# V001.net
KiCad netlist of a schematic drawn in EAGLE
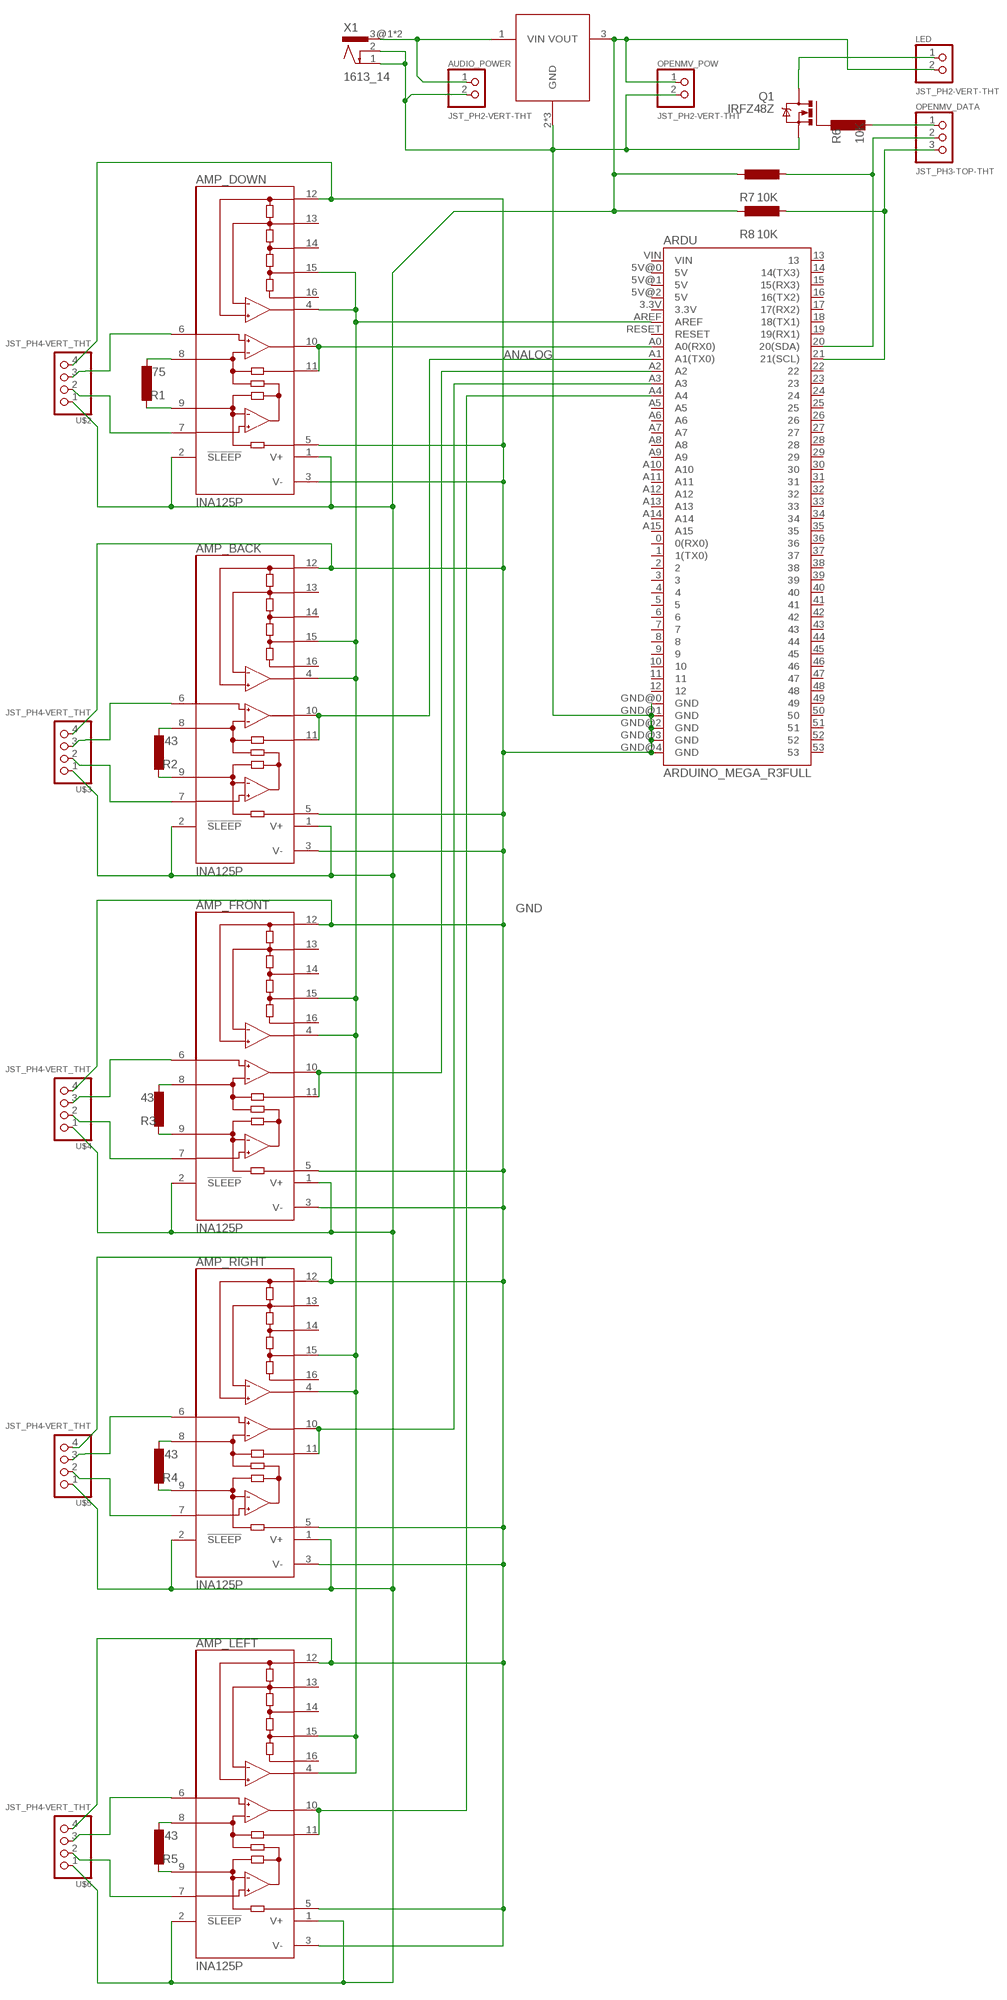
[diagram p0: schematic, sheet 1]

(export (version "E")
  (design (tool "Eeschema 10.0.6"))
  (components
    (comp (ref "AMP_BACK")
      (value "INA125P")
      (footprint "eagle-import:DIL16")
      (fields (field (name "MF") "TEXAS INSTRUMENT CONNECTORS"))
      (libsource (lib "eagle-import") (part "INA125P"))
    )
    (comp (ref "AMP_DOWN")
      (value "INA125P")
      (footprint "eagle-import:DIL16")
      (fields (field (name "MF") "TEXAS INSTRUMENT CONNECTORS"))
      (libsource (lib "eagle-import") (part "INA125P"))
    )
    (comp (ref "AMP_FRONT")
      (value "INA125P")
      (footprint "eagle-import:DIL16")
      (fields (field (name "MF") "TEXAS INSTRUMENT CONNECTORS"))
      (libsource (lib "eagle-import") (part "INA125P"))
    )
    (comp (ref "AMP_LEFT")
      (value "INA125P")
      (footprint "eagle-import:DIL16")
      (fields (field (name "MF") "TEXAS INSTRUMENT CONNECTORS"))
      (libsource (lib "eagle-import") (part "INA125P"))
    )
    (comp (ref "AMP_RIGHT")
      (value "INA125P")
      (footprint "eagle-import:DIL16")
      (fields (field (name "MF") "TEXAS INSTRUMENT CONNECTORS"))
      (libsource (lib "eagle-import") (part "INA125P"))
    )
    (comp (ref "ARDU")
      (value "ARDUINO_MEGA_R3FULL")
      (footprint "eagle-import:ARDUINO_MEGA")
      (libsource (lib "eagle-import") (part "ARDUINO_MEGA_R3FULL"))
    )
    (comp (ref "AUDIO_POWER")
      (value "JST_PH2-VERT-THT")
      (footprint "eagle-import:B2B-PH-K-S")
      (libsource (lib "eagle-import") (part "JST_PH2-VERT-THT"))
    )
    (comp (ref "LED")
      (value "JST_PH2-VERT-THT")
      (footprint "eagle-import:B2B-PH-K-S")
      (libsource (lib "eagle-import") (part "JST_PH2-VERT-THT"))
    )
    (comp (ref "OPENMV_DATA")
      (value "JST_PH3-TOP-THT")
      (footprint "eagle-import:B3B-PH-K-S")
      (libsource (lib "eagle-import") (part "JST_PH3-TOP-THT"))
    )
    (comp (ref "OPENMV_POW")
      (value "JST_PH2-VERT-THT")
      (footprint "eagle-import:B2B-PH-K-S")
      (libsource (lib "eagle-import") (part "JST_PH2-VERT-THT"))
    )
    (comp (ref "Q1")
      (value "IRFZ48Z")
      (footprint "eagle-import:TO220BH")
      (libsource (lib "eagle-import") (part "IRFZ48Z"))
    )
    (comp (ref "R1")
      (value "75")
      (footprint "eagle-import:0207_10")
      (libsource (lib "eagle-import") (part "L-EU0207/10"))
    )
    (comp (ref "R2")
      (value "43")
      (footprint "eagle-import:0207_10")
      (libsource (lib "eagle-import") (part "L-EU0207/10"))
    )
    (comp (ref "R3")
      (value "43")
      (footprint "eagle-import:0207_10")
      (libsource (lib "eagle-import") (part "L-EU0207/10"))
    )
    (comp (ref "R4")
      (value "43")
      (footprint "eagle-import:0207_10")
      (libsource (lib "eagle-import") (part "L-EU0207/10"))
    )
    (comp (ref "R5")
      (value "43")
      (footprint "eagle-import:0207_10")
      (libsource (lib "eagle-import") (part "L-EU0207/10"))
    )
    (comp (ref "R6")
      (value "10K")
      (footprint "eagle-import:0207_10")
      (libsource (lib "eagle-import") (part "L-EU0207/10"))
    )
    (comp (ref "R7")
      (value "10K")
      (footprint "eagle-import:0207_10")
      (libsource (lib "eagle-import") (part "L-EU0207/10"))
    )
    (comp (ref "R8")
      (value "10K")
      (footprint "eagle-import:0207_10")
      (libsource (lib "eagle-import") (part "L-EU0207/10"))
    )
    (comp (ref "U$1")
      (value "TL780")
      (footprint "eagle-import:TO254P1651X1067X470-3")
      (libsource (lib "eagle-import") (part "TL780"))
    )
    (comp (ref "U$2")
      (value "JST_PH4-VERT_THT")
      (footprint "eagle-import:B4B-PH-K-S")
      (libsource (lib "eagle-import") (part "JST_PH4-VERT_THT"))
    )
    (comp (ref "U$3")
      (value "JST_PH4-VERT_THT")
      (footprint "eagle-import:B4B-PH-K-S")
      (libsource (lib "eagle-import") (part "JST_PH4-VERT_THT"))
    )
    (comp (ref "U$4")
      (value "JST_PH4-VERT_THT")
      (footprint "eagle-import:B4B-PH-K-S")
      (libsource (lib "eagle-import") (part "JST_PH4-VERT_THT"))
    )
    (comp (ref "U$5")
      (value "JST_PH4-VERT_THT")
      (footprint "eagle-import:B4B-PH-K-S")
      (libsource (lib "eagle-import") (part "JST_PH4-VERT_THT"))
    )
    (comp (ref "U$6")
      (value "JST_PH4-VERT_THT")
      (footprint "eagle-import:B4B-PH-K-S")
      (libsource (lib "eagle-import") (part "JST_PH4-VERT_THT"))
    )
    (comp (ref "X1")
      (value "1613_14")
      (footprint "eagle-import:1613_14")
      (fields (field (name "MF") "LUMBERG") (field (name "MPN") "1613 14"))
      (libsource (lib "eagle-import") (part "1613_14"))
    )
  )
  (nets
    (net (code "1") (name "/ANALOG") (class "Default")
      (node (ref "AMP_DOWN") (pin "10") (pinfunction "OUT_10") (pintype "output"))
      (node (ref "AMP_DOWN") (pin "11") (pinfunction "SENSE_11") (pintype "passive"))
      (node (ref "ARDU") (pin "A0") (pinfunction "A0(RX0)_A0") (pintype "bidirectional"))
    )
    (net (code "2") (name "/GND") (class "Default")
      (node (ref "AMP_BACK") (pin "12") (pinfunction "REFCOM_12") (pintype "passive"))
      (node (ref "AMP_BACK") (pin "3") (pinfunction "V-_3") (pintype "power_in"))
      (node (ref "AMP_BACK") (pin "5") (pinfunction "REF_5") (pintype "passive"))
      (node (ref "AMP_DOWN") (pin "12") (pinfunction "REFCOM_12") (pintype "passive"))
      (node (ref "AMP_DOWN") (pin "3") (pinfunction "V-_3") (pintype "power_in"))
      (node (ref "AMP_DOWN") (pin "5") (pinfunction "REF_5") (pintype "passive"))
      (node (ref "AMP_FRONT") (pin "12") (pinfunction "REFCOM_12") (pintype "passive"))
      (node (ref "AMP_FRONT") (pin "3") (pinfunction "V-_3") (pintype "power_in"))
      (node (ref "AMP_FRONT") (pin "5") (pinfunction "REF_5") (pintype "passive"))
      (node (ref "AMP_LEFT") (pin "12") (pinfunction "REFCOM_12") (pintype "passive"))
      (node (ref "AMP_LEFT") (pin "3") (pinfunction "V-_3") (pintype "power_in"))
      (node (ref "AMP_LEFT") (pin "5") (pinfunction "REF_5") (pintype "passive"))
      (node (ref "AMP_RIGHT") (pin "12") (pinfunction "REFCOM_12") (pintype "passive"))
      (node (ref "AMP_RIGHT") (pin "3") (pinfunction "V-_3") (pintype "power_in"))
      (node (ref "AMP_RIGHT") (pin "5") (pinfunction "REF_5") (pintype "passive"))
      (node (ref "ARDU") (pin "GND@0") (pinfunction "GND_GND@0") (pintype "bidirectional"))
      (node (ref "ARDU") (pin "GND@1") (pinfunction "GND_GND@1") (pintype "bidirectional"))
      (node (ref "ARDU") (pin "GND@2") (pinfunction "GND_GND@2") (pintype "bidirectional"))
      (node (ref "ARDU") (pin "GND@3") (pinfunction "GND_GND@3") (pintype "bidirectional"))
      (node (ref "ARDU") (pin "GND@4") (pinfunction "GND_GND@4") (pintype "bidirectional"))
      (node (ref "AUDIO_POWER") (pin "2") (pinfunction "2_2") (pintype "passive"))
      (node (ref "OPENMV_POW") (pin "2") (pinfunction "2_2") (pintype "passive"))
      (node (ref "Q1") (pin "S") (pinfunction "S_S") (pintype "passive"))
      (node (ref "U$1") (pin "2") (pinfunction "GND_2") (pintype "bidirectional"))
      (node (ref "U$1") (pin "4") (pinfunction "GND_4") (pintype "bidirectional"))
      (node (ref "U$1") (pin "4.1") (pinfunction "GND_4.1") (pintype "bidirectional"))
      (node (ref "U$2") (pin "4") (pinfunction "4_4") (pintype "passive"))
      (node (ref "U$3") (pin "4") (pinfunction "4_4") (pintype "passive"))
      (node (ref "U$4") (pin "4") (pinfunction "4_4") (pintype "passive"))
      (node (ref "U$5") (pin "4") (pinfunction "4_4") (pintype "passive"))
      (node (ref "U$6") (pin "4") (pinfunction "4_4") (pintype "passive"))
      (node (ref "X1") (pin "1") (pinfunction "1_1") (pintype "passive"))
      (node (ref "X1") (pin "2") (pinfunction "2_2") (pintype "passive"))
    )
    (net (code "3") (name "Net-(AMP_BACK-+IN)") (class "Default")
      (node (ref "AMP_BACK") (pin "6") (pinfunction "+IN_6") (pintype "input"))
      (node (ref "U$3") (pin "3") (pinfunction "3_3") (pintype "passive"))
    )
    (net (code "4") (name "Net-(AMP_BACK--IN)") (class "Default")
      (node (ref "AMP_BACK") (pin "7") (pinfunction "-IN_7") (pintype "input"))
      (node (ref "U$3") (pin "2") (pinfunction "2_2") (pintype "passive"))
    )
    (net (code "5") (name "Net-(AMP_BACK-OUT)") (class "Default")
      (node (ref "AMP_BACK") (pin "10") (pinfunction "OUT_10") (pintype "output"))
      (node (ref "AMP_BACK") (pin "11") (pinfunction "SENSE_11") (pintype "passive"))
      (node (ref "ARDU") (pin "A1") (pinfunction "A1(TX0)_A1") (pintype "bidirectional"))
    )
    (net (code "6") (name "Net-(AMP_BACK-REF5)") (class "Default")
      (node (ref "AMP_BACK") (pin "15") (pinfunction "REF5_15") (pintype "output"))
      (node (ref "AMP_BACK") (pin "4") (pinfunction "REFOUT_4") (pintype "output"))
      (node (ref "AMP_DOWN") (pin "15") (pinfunction "REF5_15") (pintype "output"))
      (node (ref "AMP_DOWN") (pin "4") (pinfunction "REFOUT_4") (pintype "output"))
      (node (ref "AMP_FRONT") (pin "15") (pinfunction "REF5_15") (pintype "output"))
      (node (ref "AMP_FRONT") (pin "4") (pinfunction "REFOUT_4") (pintype "output"))
      (node (ref "AMP_LEFT") (pin "15") (pinfunction "REF5_15") (pintype "output"))
      (node (ref "AMP_LEFT") (pin "4") (pinfunction "REFOUT_4") (pintype "output"))
      (node (ref "AMP_RIGHT") (pin "15") (pinfunction "REF5_15") (pintype "output"))
      (node (ref "AMP_RIGHT") (pin "4") (pinfunction "REFOUT_4") (pintype "output"))
      (node (ref "ARDU") (pin "AREF") (pinfunction "AREF_AREF") (pintype "bidirectional"))
    )
    (net (code "7") (name "Net-(AMP_BACK-RG-Pad8)") (class "Default")
      (node (ref "AMP_BACK") (pin "8") (pinfunction "RG_8") (pintype "passive"))
      (node (ref "R2") (pin "2") (pinfunction "2_2") (pintype "passive"))
    )
    (net (code "8") (name "Net-(AMP_BACK-RG-Pad9)") (class "Default")
      (node (ref "AMP_BACK") (pin "9") (pinfunction "RG_9") (pintype "passive"))
      (node (ref "R2") (pin "1") (pinfunction "1_1") (pintype "passive"))
    )
    (net (code "9") (name "Net-(AMP_BACK-V+)") (class "Default")
      (node (ref "AMP_BACK") (pin "1") (pinfunction "V+_1") (pintype "power_in"))
      (node (ref "AMP_BACK") (pin "2") (pinfunction "~{SLEEP}_2") (pintype "input"))
      (node (ref "AMP_DOWN") (pin "1") (pinfunction "V+_1") (pintype "power_in"))
      (node (ref "AMP_DOWN") (pin "2") (pinfunction "~{SLEEP}_2") (pintype "input"))
      (node (ref "AMP_FRONT") (pin "1") (pinfunction "V+_1") (pintype "power_in"))
      (node (ref "AMP_FRONT") (pin "2") (pinfunction "~{SLEEP}_2") (pintype "input"))
      (node (ref "AMP_LEFT") (pin "1") (pinfunction "V+_1") (pintype "power_in"))
      (node (ref "AMP_LEFT") (pin "2") (pinfunction "~{SLEEP}_2") (pintype "input"))
      (node (ref "AMP_RIGHT") (pin "1") (pinfunction "V+_1") (pintype "power_in"))
      (node (ref "AMP_RIGHT") (pin "2") (pinfunction "~{SLEEP}_2") (pintype "input"))
      (node (ref "LED") (pin "2") (pinfunction "2_2") (pintype "passive"))
      (node (ref "OPENMV_POW") (pin "1") (pinfunction "1_1") (pintype "passive"))
      (node (ref "R7") (pin "1") (pinfunction "1_1") (pintype "passive"))
      (node (ref "R8") (pin "1") (pinfunction "1_1") (pintype "passive"))
      (node (ref "U$1") (pin "3") (pinfunction "VOUT_3") (pintype "bidirectional"))
      (node (ref "U$2") (pin "1") (pinfunction "1_1") (pintype "passive"))
      (node (ref "U$3") (pin "1") (pinfunction "1_1") (pintype "passive"))
      (node (ref "U$4") (pin "1") (pinfunction "1_1") (pintype "passive"))
      (node (ref "U$5") (pin "1") (pinfunction "1_1") (pintype "passive"))
      (node (ref "U$6") (pin "1") (pinfunction "1_1") (pintype "passive"))
    )
    (net (code "10") (name "Net-(AMP_DOWN-+IN)") (class "Default")
      (node (ref "AMP_DOWN") (pin "6") (pinfunction "+IN_6") (pintype "input"))
      (node (ref "U$2") (pin "3") (pinfunction "3_3") (pintype "passive"))
    )
    (net (code "11") (name "Net-(AMP_DOWN--IN)") (class "Default")
      (node (ref "AMP_DOWN") (pin "7") (pinfunction "-IN_7") (pintype "input"))
      (node (ref "U$2") (pin "2") (pinfunction "2_2") (pintype "passive"))
    )
    (net (code "12") (name "Net-(AMP_DOWN-RG-Pad8)") (class "Default")
      (node (ref "AMP_DOWN") (pin "8") (pinfunction "RG_8") (pintype "passive"))
      (node (ref "R1") (pin "2") (pinfunction "2_2") (pintype "passive"))
    )
    (net (code "13") (name "Net-(AMP_DOWN-RG-Pad9)") (class "Default")
      (node (ref "AMP_DOWN") (pin "9") (pinfunction "RG_9") (pintype "passive"))
      (node (ref "R1") (pin "1") (pinfunction "1_1") (pintype "passive"))
    )
    (net (code "14") (name "Net-(AMP_FRONT-+IN)") (class "Default")
      (node (ref "AMP_FRONT") (pin "6") (pinfunction "+IN_6") (pintype "input"))
      (node (ref "U$4") (pin "3") (pinfunction "3_3") (pintype "passive"))
    )
    (net (code "15") (name "Net-(AMP_FRONT--IN)") (class "Default")
      (node (ref "AMP_FRONT") (pin "7") (pinfunction "-IN_7") (pintype "input"))
      (node (ref "U$4") (pin "2") (pinfunction "2_2") (pintype "passive"))
    )
    (net (code "16") (name "Net-(AMP_FRONT-OUT)") (class "Default")
      (node (ref "AMP_FRONT") (pin "10") (pinfunction "OUT_10") (pintype "output"))
      (node (ref "AMP_FRONT") (pin "11") (pinfunction "SENSE_11") (pintype "passive"))
      (node (ref "ARDU") (pin "A2") (pinfunction "A2_A2") (pintype "bidirectional"))
    )
    (net (code "17") (name "Net-(AMP_FRONT-RG-Pad8)") (class "Default")
      (node (ref "AMP_FRONT") (pin "8") (pinfunction "RG_8") (pintype "passive"))
      (node (ref "R3") (pin "2") (pinfunction "2_2") (pintype "passive"))
    )
    (net (code "18") (name "Net-(AMP_FRONT-RG-Pad9)") (class "Default")
      (node (ref "AMP_FRONT") (pin "9") (pinfunction "RG_9") (pintype "passive"))
      (node (ref "R3") (pin "1") (pinfunction "1_1") (pintype "passive"))
    )
    (net (code "19") (name "Net-(AMP_LEFT-+IN)") (class "Default")
      (node (ref "AMP_LEFT") (pin "6") (pinfunction "+IN_6") (pintype "input"))
      (node (ref "U$6") (pin "3") (pinfunction "3_3") (pintype "passive"))
    )
    (net (code "20") (name "Net-(AMP_LEFT--IN)") (class "Default")
      (node (ref "AMP_LEFT") (pin "7") (pinfunction "-IN_7") (pintype "input"))
      (node (ref "U$6") (pin "2") (pinfunction "2_2") (pintype "passive"))
    )
    (net (code "21") (name "Net-(AMP_LEFT-OUT)") (class "Default")
      (node (ref "AMP_LEFT") (pin "10") (pinfunction "OUT_10") (pintype "output"))
      (node (ref "AMP_LEFT") (pin "11") (pinfunction "SENSE_11") (pintype "passive"))
      (node (ref "ARDU") (pin "A4") (pinfunction "A4_A4") (pintype "bidirectional"))
    )
    (net (code "22") (name "Net-(AMP_LEFT-RG-Pad8)") (class "Default")
      (node (ref "AMP_LEFT") (pin "8") (pinfunction "RG_8") (pintype "passive"))
      (node (ref "R5") (pin "2") (pinfunction "2_2") (pintype "passive"))
    )
    (net (code "23") (name "Net-(AMP_LEFT-RG-Pad9)") (class "Default")
      (node (ref "AMP_LEFT") (pin "9") (pinfunction "RG_9") (pintype "passive"))
      (node (ref "R5") (pin "1") (pinfunction "1_1") (pintype "passive"))
    )
    (net (code "24") (name "Net-(AMP_RIGHT-+IN)") (class "Default")
      (node (ref "AMP_RIGHT") (pin "6") (pinfunction "+IN_6") (pintype "input"))
      (node (ref "U$5") (pin "3") (pinfunction "3_3") (pintype "passive"))
    )
    (net (code "25") (name "Net-(AMP_RIGHT--IN)") (class "Default")
      (node (ref "AMP_RIGHT") (pin "7") (pinfunction "-IN_7") (pintype "input"))
      (node (ref "U$5") (pin "2") (pinfunction "2_2") (pintype "passive"))
    )
    (net (code "26") (name "Net-(AMP_RIGHT-OUT)") (class "Default")
      (node (ref "AMP_RIGHT") (pin "10") (pinfunction "OUT_10") (pintype "output"))
      (node (ref "AMP_RIGHT") (pin "11") (pinfunction "SENSE_11") (pintype "passive"))
      (node (ref "ARDU") (pin "A3") (pinfunction "A3_A3") (pintype "bidirectional"))
    )
    (net (code "27") (name "Net-(AMP_RIGHT-RG-Pad8)") (class "Default")
      (node (ref "AMP_RIGHT") (pin "8") (pinfunction "RG_8") (pintype "passive"))
      (node (ref "R4") (pin "2") (pinfunction "2_2") (pintype "passive"))
    )
    (net (code "28") (name "Net-(AMP_RIGHT-RG-Pad9)") (class "Default")
      (node (ref "AMP_RIGHT") (pin "9") (pinfunction "RG_9") (pintype "passive"))
      (node (ref "R4") (pin "1") (pinfunction "1_1") (pintype "passive"))
    )
    (net (code "29") (name "Net-(ARDU-20(SDA))") (class "Default")
      (node (ref "ARDU") (pin "20") (pinfunction "20(SDA)_20") (pintype "bidirectional"))
      (node (ref "OPENMV_DATA") (pin "2") (pinfunction "2_2") (pintype "passive"))
      (node (ref "R7") (pin "2") (pinfunction "2_2") (pintype "passive"))
    )
    (net (code "30") (name "Net-(ARDU-21(SCL))") (class "Default")
      (node (ref "ARDU") (pin "21") (pinfunction "21(SCL)_21") (pintype "bidirectional"))
      (node (ref "OPENMV_DATA") (pin "3") (pinfunction "3_3") (pintype "passive"))
      (node (ref "R8") (pin "2") (pinfunction "2_2") (pintype "passive"))
    )
    (net (code "31") (name "Net-(LED-Pad1)") (class "Default")
      (node (ref "LED") (pin "1") (pinfunction "1_1") (pintype "passive"))
      (node (ref "Q1") (pin "D") (pinfunction "D_D") (pintype "passive"))
    )
    (net (code "32") (name "Net-(OPENMV_DATA-Pad1)") (class "Default")
      (node (ref "OPENMV_DATA") (pin "1") (pinfunction "1_1") (pintype "passive"))
      (node (ref "R6") (pin "2") (pinfunction "2_2") (pintype "passive"))
    )
    (net (code "33") (name "Net-(Q1-PadG)") (class "Default")
      (node (ref "Q1") (pin "G") (pinfunction "G_G") (pintype "passive"))
      (node (ref "R6") (pin "1") (pinfunction "1_1") (pintype "passive"))
    )
    (net (code "34") (name "Net-(U$1-VIN)") (class "Default")
      (node (ref "AUDIO_POWER") (pin "1") (pinfunction "1_1") (pintype "passive"))
      (node (ref "U$1") (pin "1") (pinfunction "VIN_1") (pintype "bidirectional"))
      (node (ref "X1") (pin "3@1") (pinfunction "3_3@1") (pintype "passive"))
      (node (ref "X1") (pin "3@2") (pinfunction "3_3@2") (pintype "passive"))
    )
    (net (code "35") (name "unconnected-(AMP_BACK-REF2.5-Pad14)") (class "Default")
      (node (ref "AMP_BACK") (pin "14") (pinfunction "REF2.5_14") (pintype "output"))
    )
    (net (code "36") (name "unconnected-(AMP_BACK-REF10-Pad16)") (class "Default")
      (node (ref "AMP_BACK") (pin "16") (pinfunction "REF10_16") (pintype "output"))
    )
    (net (code "37") (name "unconnected-(AMP_BACK-REFBG-Pad13)") (class "Default")
      (node (ref "AMP_BACK") (pin "13") (pinfunction "REFBG_13") (pintype "output"))
    )
    (net (code "38") (name "unconnected-(AMP_DOWN-REF2.5-Pad14)") (class "Default")
      (node (ref "AMP_DOWN") (pin "14") (pinfunction "REF2.5_14") (pintype "output"))
    )
    (net (code "39") (name "unconnected-(AMP_DOWN-REF10-Pad16)") (class "Default")
      (node (ref "AMP_DOWN") (pin "16") (pinfunction "REF10_16") (pintype "output"))
    )
    (net (code "40") (name "unconnected-(AMP_DOWN-REFBG-Pad13)") (class "Default")
      (node (ref "AMP_DOWN") (pin "13") (pinfunction "REFBG_13") (pintype "output"))
    )
    (net (code "41") (name "unconnected-(AMP_FRONT-REF2.5-Pad14)") (class "Default")
      (node (ref "AMP_FRONT") (pin "14") (pinfunction "REF2.5_14") (pintype "output"))
    )
    (net (code "42") (name "unconnected-(AMP_FRONT-REF10-Pad16)") (class "Default")
      (node (ref "AMP_FRONT") (pin "16") (pinfunction "REF10_16") (pintype "output"))
    )
    (net (code "43") (name "unconnected-(AMP_FRONT-REFBG-Pad13)") (class "Default")
      (node (ref "AMP_FRONT") (pin "13") (pinfunction "REFBG_13") (pintype "output"))
    )
    (net (code "44") (name "unconnected-(AMP_LEFT-REF2.5-Pad14)") (class "Default")
      (node (ref "AMP_LEFT") (pin "14") (pinfunction "REF2.5_14") (pintype "output"))
    )
    (net (code "45") (name "unconnected-(AMP_LEFT-REF10-Pad16)") (class "Default")
      (node (ref "AMP_LEFT") (pin "16") (pinfunction "REF10_16") (pintype "output"))
    )
    (net (code "46") (name "unconnected-(AMP_LEFT-REFBG-Pad13)") (class "Default")
      (node (ref "AMP_LEFT") (pin "13") (pinfunction "REFBG_13") (pintype "output"))
    )
    (net (code "47") (name "unconnected-(AMP_RIGHT-REF2.5-Pad14)") (class "Default")
      (node (ref "AMP_RIGHT") (pin "14") (pinfunction "REF2.5_14") (pintype "output"))
    )
    (net (code "48") (name "unconnected-(AMP_RIGHT-REF10-Pad16)") (class "Default")
      (node (ref "AMP_RIGHT") (pin "16") (pinfunction "REF10_16") (pintype "output"))
    )
    (net (code "49") (name "unconnected-(AMP_RIGHT-REFBG-Pad13)") (class "Default")
      (node (ref "AMP_RIGHT") (pin "13") (pinfunction "REFBG_13") (pintype "output"))
    )
    (net (code "50") (name "unconnected-(ARDU-0(RX0)-Pad0)") (class "Default")
      (node (ref "ARDU") (pin "0") (pinfunction "0(RX0)_0") (pintype "bidirectional"))
    )
    (net (code "51") (name "unconnected-(ARDU-1(TX0)-Pad1)") (class "Default")
      (node (ref "ARDU") (pin "1") (pinfunction "1(TX0)_1") (pintype "bidirectional"))
    )
    (net (code "52") (name "unconnected-(ARDU-5V-Pad5V@0)") (class "Default")
      (node (ref "ARDU") (pin "5V@0") (pinfunction "5V_5V@0") (pintype "bidirectional"))
    )
    (net (code "53") (name "unconnected-(ARDU-5V-Pad5V@1)") (class "Default")
      (node (ref "ARDU") (pin "5V@1") (pinfunction "5V_5V@1") (pintype "bidirectional"))
    )
    (net (code "54") (name "unconnected-(ARDU-5V-Pad5V@2)") (class "Default")
      (node (ref "ARDU") (pin "5V@2") (pinfunction "5V_5V@2") (pintype "bidirectional"))
    )
    (net (code "55") (name "unconnected-(ARDU-14(TX3)-Pad14)") (class "Default")
      (node (ref "ARDU") (pin "14") (pinfunction "14(TX3)_14") (pintype "bidirectional"))
    )
    (net (code "56") (name "unconnected-(ARDU-15(RX3)-Pad15)") (class "Default")
      (node (ref "ARDU") (pin "15") (pinfunction "15(RX3)_15") (pintype "bidirectional"))
    )
    (net (code "57") (name "unconnected-(ARDU-16(TX2)-Pad16)") (class "Default")
      (node (ref "ARDU") (pin "16") (pinfunction "16(TX2)_16") (pintype "bidirectional"))
    )
    (net (code "58") (name "unconnected-(ARDU-17(RX2)-Pad17)") (class "Default")
      (node (ref "ARDU") (pin "17") (pinfunction "17(RX2)_17") (pintype "bidirectional"))
    )
    (net (code "59") (name "unconnected-(ARDU-18(TX1)-Pad18)") (class "Default")
      (node (ref "ARDU") (pin "18") (pinfunction "18(TX1)_18") (pintype "bidirectional"))
    )
    (net (code "60") (name "unconnected-(ARDU-19(RX1)-Pad19)") (class "Default")
      (node (ref "ARDU") (pin "19") (pinfunction "19(RX1)_19") (pintype "bidirectional"))
    )
    (net (code "61") (name "unconnected-(ARDU-Pad2)") (class "Default")
      (node (ref "ARDU") (pin "2") (pinfunction "2_2") (pintype "bidirectional"))
    )
    (net (code "62") (name "unconnected-(ARDU-Pad3)") (class "Default")
      (node (ref "ARDU") (pin "3") (pinfunction "3_3") (pintype "bidirectional"))
    )
    (net (code "63") (name "unconnected-(ARDU-Pad3.3V)") (class "Default")
      (node (ref "ARDU") (pin "3.3V") (pinfunction "3.3V_3.3V") (pintype "bidirectional"))
    )
    (net (code "64") (name "unconnected-(ARDU-Pad4)") (class "Default")
      (node (ref "ARDU") (pin "4") (pinfunction "4_4") (pintype "bidirectional"))
    )
    (net (code "65") (name "unconnected-(ARDU-Pad5)") (class "Default")
      (node (ref "ARDU") (pin "5") (pinfunction "5_5") (pintype "bidirectional"))
    )
    (net (code "66") (name "unconnected-(ARDU-Pad6)") (class "Default")
      (node (ref "ARDU") (pin "6") (pinfunction "6_6") (pintype "bidirectional"))
    )
    (net (code "67") (name "unconnected-(ARDU-Pad7)") (class "Default")
      (node (ref "ARDU") (pin "7") (pinfunction "7_7") (pintype "bidirectional"))
    )
    (net (code "68") (name "unconnected-(ARDU-Pad8)") (class "Default")
      (node (ref "ARDU") (pin "8") (pinfunction "8_8") (pintype "bidirectional"))
    )
    (net (code "69") (name "unconnected-(ARDU-Pad9)") (class "Default")
      (node (ref "ARDU") (pin "9") (pinfunction "9_9") (pintype "bidirectional"))
    )
    (net (code "70") (name "unconnected-(ARDU-Pad10)") (class "Default")
      (node (ref "ARDU") (pin "10") (pinfunction "10_10") (pintype "bidirectional"))
    )
    (net (code "71") (name "unconnected-(ARDU-Pad11)") (class "Default")
      (node (ref "ARDU") (pin "11") (pinfunction "11_11") (pintype "bidirectional"))
    )
    (net (code "72") (name "unconnected-(ARDU-Pad12)") (class "Default")
      (node (ref "ARDU") (pin "12") (pinfunction "12_12") (pintype "bidirectional"))
    )
    (net (code "73") (name "unconnected-(ARDU-Pad13)") (class "Default")
      (node (ref "ARDU") (pin "13") (pinfunction "13_13") (pintype "bidirectional"))
    )
    (net (code "74") (name "unconnected-(ARDU-Pad22)") (class "Default")
      (node (ref "ARDU") (pin "22") (pinfunction "22_22") (pintype "bidirectional"))
    )
    (net (code "75") (name "unconnected-(ARDU-Pad23)") (class "Default")
      (node (ref "ARDU") (pin "23") (pinfunction "23_23") (pintype "bidirectional"))
    )
    (net (code "76") (name "unconnected-(ARDU-Pad24)") (class "Default")
      (node (ref "ARDU") (pin "24") (pinfunction "24_24") (pintype "bidirectional"))
    )
    (net (code "77") (name "unconnected-(ARDU-Pad25)") (class "Default")
      (node (ref "ARDU") (pin "25") (pinfunction "25_25") (pintype "bidirectional"))
    )
    (net (code "78") (name "unconnected-(ARDU-Pad26)") (class "Default")
      (node (ref "ARDU") (pin "26") (pinfunction "26_26") (pintype "bidirectional"))
    )
    (net (code "79") (name "unconnected-(ARDU-Pad27)") (class "Default")
      (node (ref "ARDU") (pin "27") (pinfunction "27_27") (pintype "bidirectional"))
    )
    (net (code "80") (name "unconnected-(ARDU-Pad28)") (class "Default")
      (node (ref "ARDU") (pin "28") (pinfunction "28_28") (pintype "bidirectional"))
    )
    (net (code "81") (name "unconnected-(ARDU-Pad29)") (class "Default")
      (node (ref "ARDU") (pin "29") (pinfunction "29_29") (pintype "bidirectional"))
    )
    (net (code "82") (name "unconnected-(ARDU-Pad30)") (class "Default")
      (node (ref "ARDU") (pin "30") (pinfunction "30_30") (pintype "bidirectional"))
    )
    (net (code "83") (name "unconnected-(ARDU-Pad31)") (class "Default")
      (node (ref "ARDU") (pin "31") (pinfunction "31_31") (pintype "bidirectional"))
    )
    (net (code "84") (name "unconnected-(ARDU-Pad32)") (class "Default")
      (node (ref "ARDU") (pin "32") (pinfunction "32_32") (pintype "bidirectional"))
    )
    (net (code "85") (name "unconnected-(ARDU-Pad33)") (class "Default")
      (node (ref "ARDU") (pin "33") (pinfunction "33_33") (pintype "bidirectional"))
    )
    (net (code "86") (name "unconnected-(ARDU-Pad34)") (class "Default")
      (node (ref "ARDU") (pin "34") (pinfunction "34_34") (pintype "bidirectional"))
    )
    (net (code "87") (name "unconnected-(ARDU-Pad35)") (class "Default")
      (node (ref "ARDU") (pin "35") (pinfunction "35_35") (pintype "bidirectional"))
    )
    (net (code "88") (name "unconnected-(ARDU-Pad36)") (class "Default")
      (node (ref "ARDU") (pin "36") (pinfunction "36_36") (pintype "bidirectional"))
    )
    (net (code "89") (name "unconnected-(ARDU-Pad37)") (class "Default")
      (node (ref "ARDU") (pin "37") (pinfunction "37_37") (pintype "bidirectional"))
    )
    (net (code "90") (name "unconnected-(ARDU-Pad38)") (class "Default")
      (node (ref "ARDU") (pin "38") (pinfunction "38_38") (pintype "bidirectional"))
    )
    (net (code "91") (name "unconnected-(ARDU-Pad39)") (class "Default")
      (node (ref "ARDU") (pin "39") (pinfunction "39_39") (pintype "bidirectional"))
    )
    (net (code "92") (name "unconnected-(ARDU-Pad40)") (class "Default")
      (node (ref "ARDU") (pin "40") (pinfunction "40_40") (pintype "bidirectional"))
    )
    (net (code "93") (name "unconnected-(ARDU-Pad41)") (class "Default")
      (node (ref "ARDU") (pin "41") (pinfunction "41_41") (pintype "bidirectional"))
    )
    (net (code "94") (name "unconnected-(ARDU-Pad42)") (class "Default")
      (node (ref "ARDU") (pin "42") (pinfunction "42_42") (pintype "bidirectional"))
    )
    (net (code "95") (name "unconnected-(ARDU-Pad43)") (class "Default")
      (node (ref "ARDU") (pin "43") (pinfunction "43_43") (pintype "bidirectional"))
    )
    (net (code "96") (name "unconnected-(ARDU-Pad44)") (class "Default")
      (node (ref "ARDU") (pin "44") (pinfunction "44_44") (pintype "bidirectional"))
    )
    (net (code "97") (name "unconnected-(ARDU-Pad45)") (class "Default")
      (node (ref "ARDU") (pin "45") (pinfunction "45_45") (pintype "bidirectional"))
    )
    (net (code "98") (name "unconnected-(ARDU-Pad46)") (class "Default")
      (node (ref "ARDU") (pin "46") (pinfunction "46_46") (pintype "bidirectional"))
    )
    (net (code "99") (name "unconnected-(ARDU-Pad47)") (class "Default")
      (node (ref "ARDU") (pin "47") (pinfunction "47_47") (pintype "bidirectional"))
    )
    (net (code "100") (name "unconnected-(ARDU-Pad48)") (class "Default")
      (node (ref "ARDU") (pin "48") (pinfunction "48_48") (pintype "bidirectional"))
    )
    (net (code "101") (name "unconnected-(ARDU-Pad49)") (class "Default")
      (node (ref "ARDU") (pin "49") (pinfunction "49_49") (pintype "bidirectional"))
    )
    (net (code "102") (name "unconnected-(ARDU-Pad50)") (class "Default")
      (node (ref "ARDU") (pin "50") (pinfunction "50_50") (pintype "bidirectional"))
    )
    (net (code "103") (name "unconnected-(ARDU-Pad51)") (class "Default")
      (node (ref "ARDU") (pin "51") (pinfunction "51_51") (pintype "bidirectional"))
    )
    (net (code "104") (name "unconnected-(ARDU-Pad52)") (class "Default")
      (node (ref "ARDU") (pin "52") (pinfunction "52_52") (pintype "bidirectional"))
    )
    (net (code "105") (name "unconnected-(ARDU-Pad53)") (class "Default")
      (node (ref "ARDU") (pin "53") (pinfunction "53_53") (pintype "bidirectional"))
    )
    (net (code "106") (name "unconnected-(ARDU-PadA5)") (class "Default")
      (node (ref "ARDU") (pin "A5") (pinfunction "A5_A5") (pintype "bidirectional"))
    )
    (net (code "107") (name "unconnected-(ARDU-PadA6)") (class "Default")
      (node (ref "ARDU") (pin "A6") (pinfunction "A6_A6") (pintype "bidirectional"))
    )
    (net (code "108") (name "unconnected-(ARDU-PadA7)") (class "Default")
      (node (ref "ARDU") (pin "A7") (pinfunction "A7_A7") (pintype "bidirectional"))
    )
    (net (code "109") (name "unconnected-(ARDU-PadA8)") (class "Default")
      (node (ref "ARDU") (pin "A8") (pinfunction "A8_A8") (pintype "bidirectional"))
    )
    (net (code "110") (name "unconnected-(ARDU-PadA9)") (class "Default")
      (node (ref "ARDU") (pin "A9") (pinfunction "A9_A9") (pintype "bidirectional"))
    )
    (net (code "111") (name "unconnected-(ARDU-PadA10)") (class "Default")
      (node (ref "ARDU") (pin "A10") (pinfunction "A10_A10") (pintype "bidirectional"))
    )
    (net (code "112") (name "unconnected-(ARDU-PadA11)") (class "Default")
      (node (ref "ARDU") (pin "A11") (pinfunction "A11_A11") (pintype "bidirectional"))
    )
    (net (code "113") (name "unconnected-(ARDU-PadA12)") (class "Default")
      (node (ref "ARDU") (pin "A12") (pinfunction "A12_A12") (pintype "bidirectional"))
    )
    (net (code "114") (name "unconnected-(ARDU-PadA13)") (class "Default")
      (node (ref "ARDU") (pin "A13") (pinfunction "A13_A13") (pintype "bidirectional"))
    )
    (net (code "115") (name "unconnected-(ARDU-PadA14)") (class "Default")
      (node (ref "ARDU") (pin "A14") (pinfunction "A14_A14") (pintype "bidirectional"))
    )
    (net (code "116") (name "unconnected-(ARDU-PadA15)") (class "Default")
      (node (ref "ARDU") (pin "A15") (pinfunction "A15_A15") (pintype "bidirectional"))
    )
    (net (code "117") (name "unconnected-(ARDU-PadRESET)") (class "Default")
      (node (ref "ARDU") (pin "RESET") (pinfunction "RESET_RESET") (pintype "bidirectional"))
    )
    (net (code "118") (name "unconnected-(ARDU-PadVIN)") (class "Default")
      (node (ref "ARDU") (pin "VIN") (pinfunction "VIN_VIN") (pintype "bidirectional"))
    )
  )
)
